# Motorsteuerung_v3.net
KiCad netlist of a schematic drawn in EAGLE
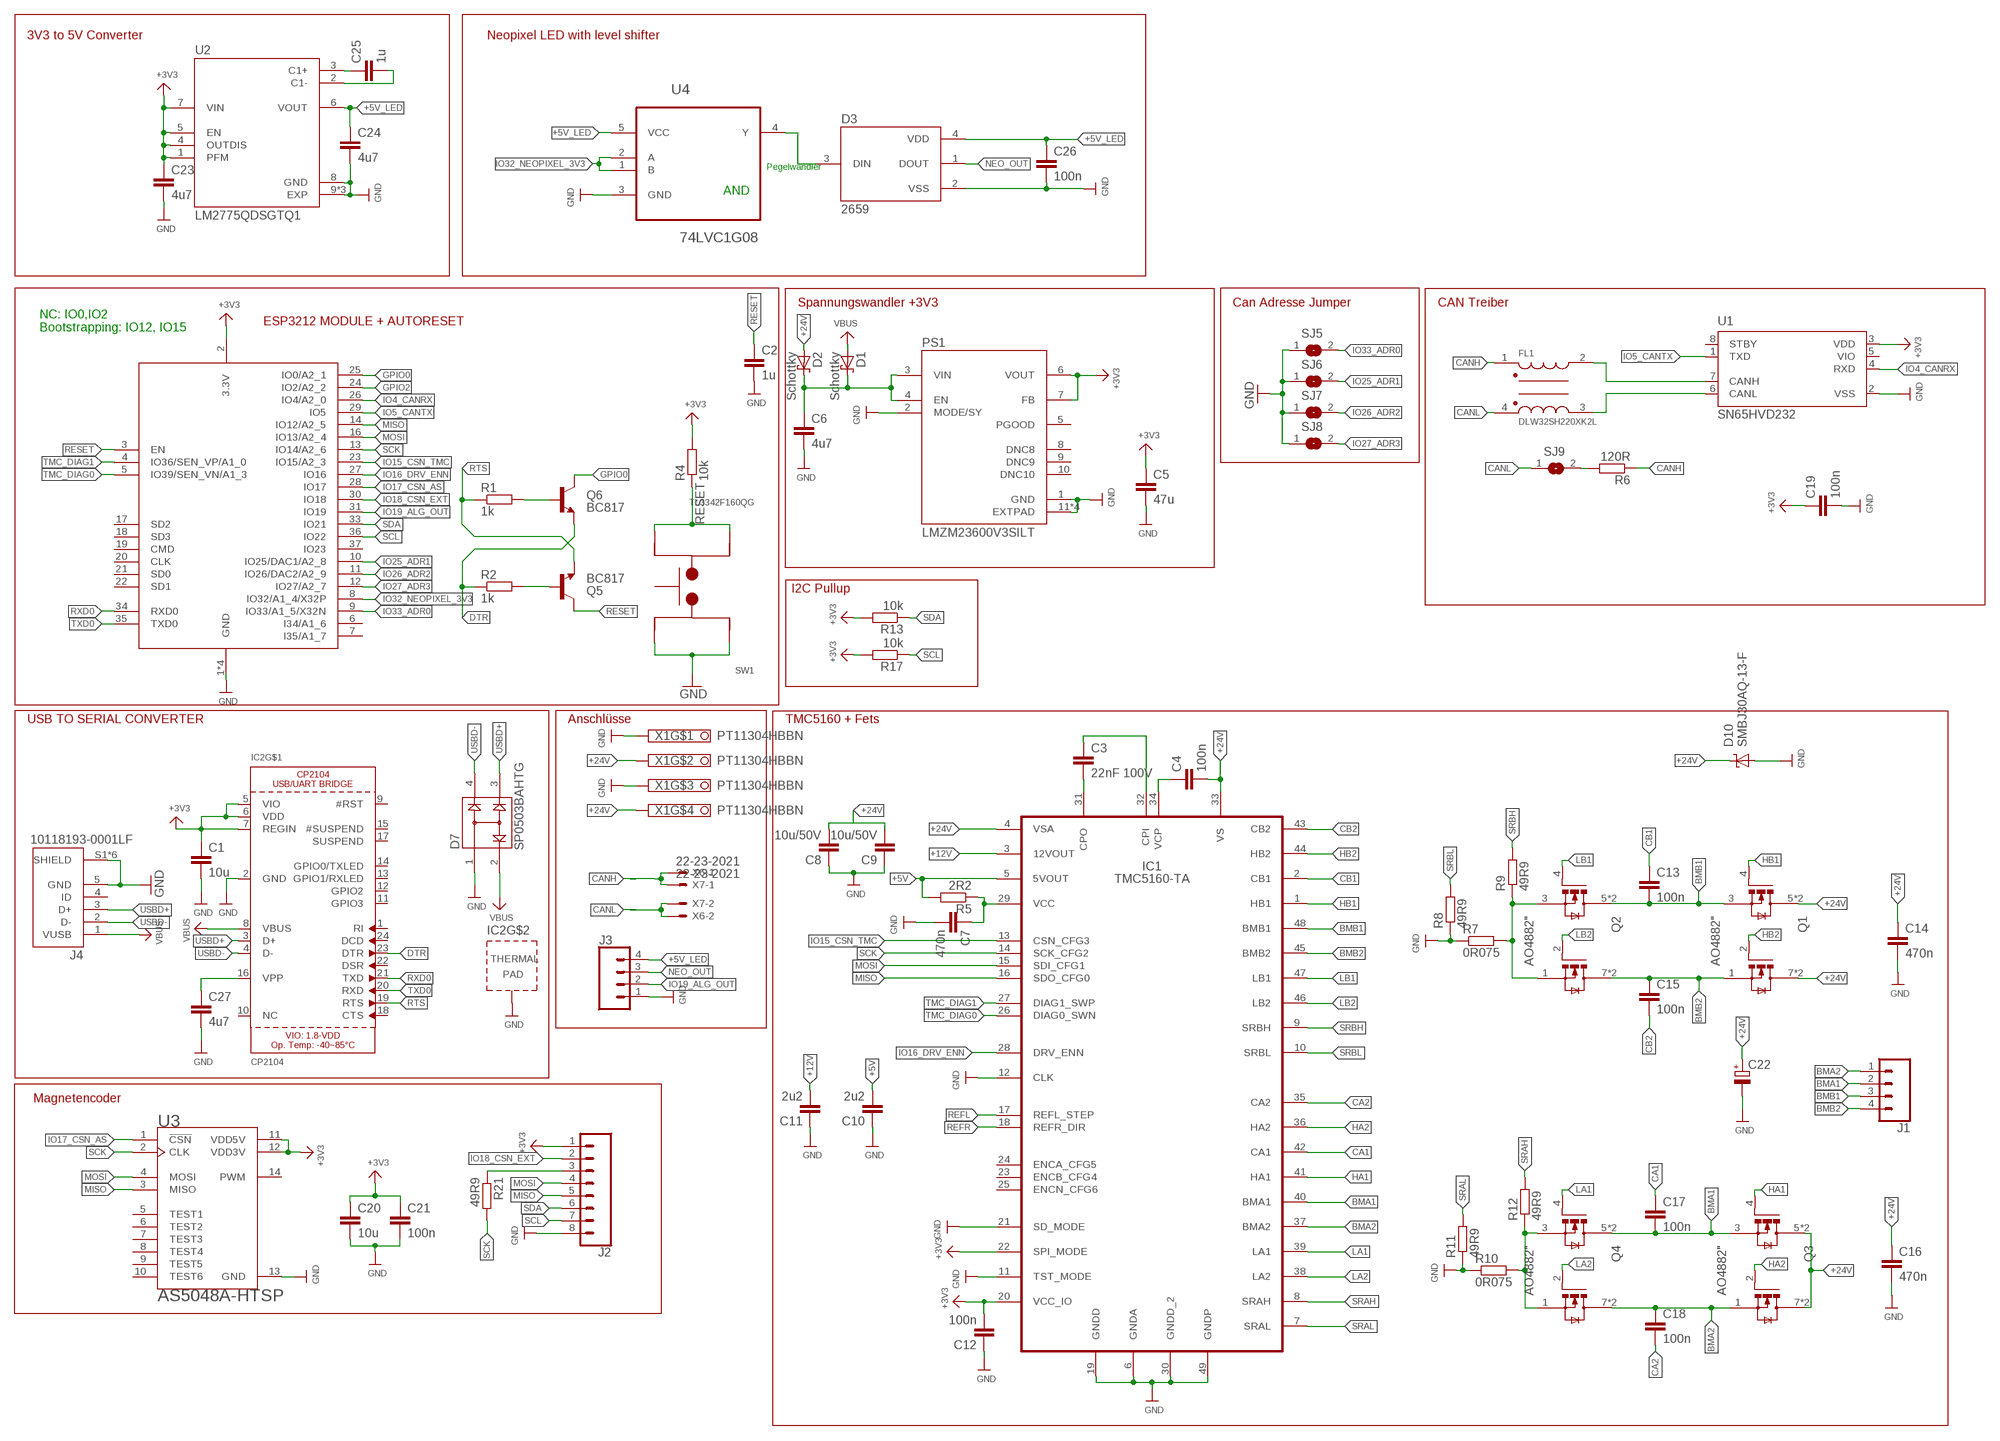
[diagram p0: schematic, sheet 1]

(export (version "E")
  (design (tool "Eeschema 10.0.6"))
  (components
    (comp (ref "C1")
      (value "10u")
      (footprint "eagle-import:C0805")
      (libsource (lib "eagle-import") (part "C-EUC0805"))
    )
    (comp (ref "C2")
      (value "1u")
      (footprint "eagle-import:C0805")
      (libsource (lib "eagle-import") (part "C-EUC0805"))
    )
    (comp (ref "C3")
      (value "22nF 100V")
      (footprint "eagle-import:C0805")
      (libsource (lib "eagle-import") (part "C-EUC0805"))
    )
    (comp (ref "C4")
      (value "100n")
      (footprint "eagle-import:C0805")
      (libsource (lib "eagle-import") (part "C-EUC0805"))
    )
    (comp (ref "C5")
      (value "47u")
      (footprint "eagle-import:C0805")
      (libsource (lib "eagle-import") (part "C-EUC0805"))
    )
    (comp (ref "C6")
      (value "4u7")
      (footprint "eagle-import:C0805")
      (libsource (lib "eagle-import") (part "C-EUC0805"))
    )
    (comp (ref "C7")
      (value "470n")
      (footprint "eagle-import:C0805")
      (libsource (lib "eagle-import") (part "C-EUC0805"))
    )
    (comp (ref "C8")
      (value "10u/50V")
      (footprint "eagle-import:C0805")
      (libsource (lib "eagle-import") (part "C-EUC0805"))
    )
    (comp (ref "C9")
      (value "10u/50V")
      (footprint "eagle-import:C0805")
      (libsource (lib "eagle-import") (part "C-EUC0805"))
    )
    (comp (ref "C10")
      (value "2u2")
      (footprint "eagle-import:C0805")
      (libsource (lib "eagle-import") (part "C-EUC0805"))
    )
    (comp (ref "C11")
      (value "2u2")
      (footprint "eagle-import:C0805")
      (libsource (lib "eagle-import") (part "C-EUC0805"))
    )
    (comp (ref "C12")
      (value "100n")
      (footprint "eagle-import:C0805")
      (libsource (lib "eagle-import") (part "C-EUC0805"))
    )
    (comp (ref "C13")
      (value "100n")
      (footprint "eagle-import:C0805")
      (libsource (lib "eagle-import") (part "C-EUC0805"))
    )
    (comp (ref "C14")
      (value "470n")
      (footprint "eagle-import:C0805")
      (libsource (lib "eagle-import") (part "C-EUC0805"))
    )
    (comp (ref "C15")
      (value "100n")
      (footprint "eagle-import:C0805")
      (libsource (lib "eagle-import") (part "C-EUC0805"))
    )
    (comp (ref "C16")
      (value "470n")
      (footprint "eagle-import:C0805")
      (libsource (lib "eagle-import") (part "C-EUC0805"))
    )
    (comp (ref "C17")
      (value "100n")
      (footprint "eagle-import:C0805")
      (libsource (lib "eagle-import") (part "C-EUC0805"))
    )
    (comp (ref "C18")
      (value "100n")
      (footprint "eagle-import:C0805")
      (libsource (lib "eagle-import") (part "C-EUC0805"))
    )
    (comp (ref "C19")
      (value "100n")
      (footprint "eagle-import:C0805")
      (libsource (lib "eagle-import") (part "C-EUC0805"))
    )
    (comp (ref "C20")
      (value "10u")
      (footprint "eagle-import:C0805")
      (libsource (lib "eagle-import") (part "C-EUC0805"))
    )
    (comp (ref "C21")
      (value "100n")
      (footprint "eagle-import:C0805")
      (libsource (lib "eagle-import") (part "C-EUC0805"))
    )
    (comp (ref "C22")
      (value "CPOL-EUE5-10.5")
      (footprint "eagle-import:E5-10,5")
      (libsource (lib "eagle-import") (part "CPOL-EUE5-10.5"))
    )
    (comp (ref "C23")
      (value "4u7")
      (footprint "eagle-import:C0805")
      (libsource (lib "eagle-import") (part "C-EUC0805"))
    )
    (comp (ref "C24")
      (value "4u7")
      (footprint "eagle-import:C0805")
      (libsource (lib "eagle-import") (part "C-EUC0805"))
    )
    (comp (ref "C25")
      (value "1u")
      (footprint "eagle-import:C0805")
      (libsource (lib "eagle-import") (part "C-EUC0805"))
    )
    (comp (ref "C26")
      (value "100n")
      (footprint "eagle-import:C0805")
      (libsource (lib "eagle-import") (part "C-EUC0805"))
    )
    (comp (ref "C27")
      (value "4u7")
      (footprint "eagle-import:C0805")
      (libsource (lib "eagle-import") (part "C-EUC0805"))
    )
    (comp (ref "D1")
      (value "Schottky")
      (footprint "eagle-import:SMB")
      (libsource (lib "eagle-import") (part "SCHOTTKY-DIODESMD"))
    )
    (comp (ref "D2")
      (value "Schottky")
      (footprint "eagle-import:SMB")
      (libsource (lib "eagle-import") (part "SCHOTTKY-DIODESMD"))
    )
    (comp (ref "D3")
      (value "2659")
      (footprint "eagle-import:2659")
      (fields (field (name "MF") "Adafruit Industries"))
      (libsource (lib "eagle-import") (part "2659"))
    )
    (comp (ref "D7")
      (value "SP0503BAHTG")
      (footprint "eagle-import:SOT143")
      (fields (field (name "MF") "Littelfuse Inc."))
      (libsource (lib "eagle-import") (part "SP0503BAHTG"))
    )
    (comp (ref "D10")
      (value "SMBJ30AQ-13-F")
      (footprint "eagle-import:SMBJ")
      (libsource (lib "eagle-import") (part "SUPPRESSOR-SMBJ"))
    )
    (comp (ref "FL1")
      (value "DLW32SH220XK2L")
      (footprint "eagle-import:FIL_DLW32SH110XK2L")
      (fields (field (name "MF") "Murata") (field (name "MP") "DLW32SH110XK2L"))
      (libsource (lib "eagle-import") (part "DLW32SH110XK2L"))
    )
    (comp (ref "IC1")
      (value "TMC5160-TA")
      (footprint "eagle-import:TQFP48-EP")
      (fields (field (name "MF") "Trinamic Motion"))
      (libsource (lib "eagle-import") (part "TMC5160-TA"))
    )
    (comp (ref "IC2")
      (value "CP2104")
      (footprint "eagle-import:QFN24_4MM_SMSC")
      (libsource (lib "eagle-import") (part "CP2104"))
    )
    (comp (ref "J1")
      (value "CONN_04")
      (footprint "eagle-import:1X04")
      (libsource (lib "eagle-import") (part "CONN_04"))
    )
    (comp (ref "J2")
      (value "CONN_08BM08B-SRSS-TB")
      (footprint "eagle-import:BM08B-SRSS-TB")
      (libsource (lib "eagle-import") (part "CONN_08BM08B-SRSS-TB"))
    )
    (comp (ref "J3")
      (value "CONN_041.27MM")
      (footprint "eagle-import:1X04_1.27MM")
      (libsource (lib "eagle-import") (part "CONN_041.27MM"))
    )
    (comp (ref "J4")
      (value "10118193-0001LF")
      (footprint "eagle-import:FCI_10118193-0001LF")
      (fields (field (name "MF") "Amphenol ICC (FCI)"))
      (libsource (lib "eagle-import") (part "10118193-0001LF"))
    )
    (comp (ref "PS1")
      (value "LMZM23600V3SILT")
      (footprint "eagle-import:CONV_LMZM23600V3SILT")
      (fields (field (name "MF") "Texas Instruments"))
      (libsource (lib "eagle-import") (part "LMZM23600V3SILT"))
    )
    (comp (ref "Q1")
      (value "AO4882\"")
      (footprint "eagle-import:SOIC8")
      (libsource (lib "eagle-import") (part "AO4882{dblquote}"))
    )
    (comp (ref "Q2")
      (value "AO4882\"")
      (footprint "eagle-import:SOIC8")
      (libsource (lib "eagle-import") (part "AO4882{dblquote}"))
    )
    (comp (ref "Q3")
      (value "AO4882\"")
      (footprint "eagle-import:SOIC8")
      (libsource (lib "eagle-import") (part "AO4882{dblquote}"))
    )
    (comp (ref "Q4")
      (value "AO4882\"")
      (footprint "eagle-import:SOIC8")
      (libsource (lib "eagle-import") (part "AO4882{dblquote}"))
    )
    (comp (ref "Q5")
      (value "BC817")
      (footprint "eagle-import:SOT23-3")
      (libsource (lib "eagle-import") (part "TRANSISTOR_NPNSOT23-3"))
    )
    (comp (ref "Q6")
      (value "BC817")
      (footprint "eagle-import:SOT23-3")
      (libsource (lib "eagle-import") (part "TRANSISTOR_NPNSOT23-3"))
    )
    (comp (ref "R1")
      (value "1k")
      (footprint "eagle-import:R0805")
      (libsource (lib "eagle-import") (part "R-EU_R0805"))
    )
    (comp (ref "R2")
      (value "1k")
      (footprint "eagle-import:R0805")
      (libsource (lib "eagle-import") (part "R-EU_R0805"))
    )
    (comp (ref "R4")
      (value "10k")
      (footprint "eagle-import:R0805")
      (libsource (lib "eagle-import") (part "R-EU_R0805"))
    )
    (comp (ref "R5")
      (value "2R2")
      (footprint "eagle-import:R0805")
      (libsource (lib "eagle-import") (part "R-EU_R0805"))
    )
    (comp (ref "R6")
      (value "120R")
      (footprint "eagle-import:R0805")
      (libsource (lib "eagle-import") (part "R-EU_R0805"))
    )
    (comp (ref "R7")
      (value "0R075")
      (footprint "eagle-import:R1206")
      (libsource (lib "eagle-import") (part "R-EU_R1206"))
    )
    (comp (ref "R8")
      (value "49R9")
      (footprint "eagle-import:R0805")
      (libsource (lib "eagle-import") (part "R-EU_R0805"))
    )
    (comp (ref "R9")
      (value "49R9")
      (footprint "eagle-import:R0805")
      (libsource (lib "eagle-import") (part "R-EU_R0805"))
    )
    (comp (ref "R10")
      (value "0R075")
      (footprint "eagle-import:R1206")
      (libsource (lib "eagle-import") (part "R-EU_R1206"))
    )
    (comp (ref "R11")
      (value "49R9")
      (footprint "eagle-import:R0805")
      (libsource (lib "eagle-import") (part "R-EU_R0805"))
    )
    (comp (ref "R12")
      (value "49R9")
      (footprint "eagle-import:R0805")
      (libsource (lib "eagle-import") (part "R-EU_R0805"))
    )
    (comp (ref "R13")
      (value "10k")
      (footprint "eagle-import:R0805")
      (libsource (lib "eagle-import") (part "R-EU_R0805"))
    )
    (comp (ref "R17")
      (value "10k")
      (footprint "eagle-import:R0805")
      (libsource (lib "eagle-import") (part "R-EU_R0805"))
    )
    (comp (ref "R21")
      (value "49R9")
      (footprint "eagle-import:R0805")
      (libsource (lib "eagle-import") (part "R-EU_R0805"))
    )
    (comp (ref "SJ5") (value "SJ") (footprint "eagle-import:SJ") (libsource (lib "eagle-import") (part "SJ")))
    (comp (ref "SJ6") (value "SJ") (footprint "eagle-import:SJ") (libsource (lib "eagle-import") (part "SJ")))
    (comp (ref "SJ7") (value "SJ") (footprint "eagle-import:SJ") (libsource (lib "eagle-import") (part "SJ")))
    (comp (ref "SJ8") (value "SJ") (footprint "eagle-import:SJ") (libsource (lib "eagle-import") (part "SJ")))
    (comp (ref "SJ9") (value "SJ") (footprint "eagle-import:SJ") (libsource (lib "eagle-import") (part "SJ")))
    (comp (ref "SW1")
      (value "TL3342F160QG")
      (footprint "eagle-import:SW_TL3342F160QG")
      (fields (field (name "MF") "E-Switch"))
      (libsource (lib "eagle-import") (part "TL3342F160QG"))
    )
    (comp (ref "U1")
      (value "SN65HVD232")
      (footprint "eagle-import:SOIC127P600X175-8N")
      (fields (field (name "MF") "Microchip") (field (name "MP") "MCP2562-E/SN"))
      (libsource (lib "eagle-import") (part "MCP2562-E/SN"))
    )
    (comp (ref "U2")
      (value "LM2775QDSGTQ1")
      (footprint "eagle-import:SON50P200X200X80-9N")
      (fields (field (name "MF") "Texas Instruments"))
      (libsource (lib "eagle-import") (part "LM2775QDSGTQ1"))
    )
    (comp (ref "U3")
      (value "AS5048A-HTSP")
      (footprint "eagle-import:SOP65P640X120-14N")
      (fields (field (name "MF") "ams"))
      (libsource (lib "eagle-import") (part "AS5048A-HTSP"))
    )
    (comp (ref "U4")
      (value "74LVC1G08")
      (footprint "eagle-import:SOT65P210X110-5N")
      (fields (field (name "MF") "Nexperia") (field (name "MP") "74LVC1G00GW"))
      (libsource (lib "eagle-import") (part "74LVC1G00GW"))
    )
    (comp (ref "X1")
      (value "PT11304HBBN")
      (footprint "eagle-import:TYP184_FT")
      (libsource (lib "eagle-import") (part "TYP184"))
    )
    (comp (ref "X2")
      (value "ESP32_WROOM32_SKINNY")
      (footprint "eagle-import:WROOM32_SKINNY")
      (libsource (lib "eagle-import") (part "ESP32_WROOM32_SKINNY"))
    )
    (comp (ref "X6")
      (value "22-23-2021")
      (footprint "eagle-import:22-23-2021")
      (fields (field (name "MF") "MOLEX"))
      (libsource (lib "eagle-import") (part "22-23-2021"))
    )
    (comp (ref "X7")
      (value "22-23-2021")
      (footprint "eagle-import:22-23-2021")
      (fields (field (name "MF") "MOLEX"))
      (libsource (lib "eagle-import") (part "22-23-2021"))
    )
  )
  (nets
    (net (code "1") (name "+3V3") (class "Default")
      (node (ref "C1") (pin "1") (pinfunction "1_1") (pintype "passive"))
      (node (ref "C12") (pin "2") (pinfunction "2_2") (pintype "passive"))
      (node (ref "C19") (pin "1") (pinfunction "1_1") (pintype "passive"))
      (node (ref "C20") (pin "1") (pinfunction "1_1") (pintype "passive"))
      (node (ref "C21") (pin "1") (pinfunction "1_1") (pintype "passive"))
      (node (ref "C23") (pin "1") (pinfunction "1_1") (pintype "passive"))
      (node (ref "C5") (pin "1") (pinfunction "1_1") (pintype "passive"))
      (node (ref "IC1") (pin "20") (pinfunction "VCC_IO_20") (pintype "power_in"))
      (node (ref "IC1") (pin "22") (pinfunction "SPI_MODE_22") (pintype "input"))
      (node (ref "IC2") (pin "5") (pinfunction "VIO_5") (pintype "power_in"))
      (node (ref "IC2") (pin "6") (pinfunction "VDD_6") (pintype "power_in"))
      (node (ref "IC2") (pin "7") (pinfunction "REGIN_7") (pintype "power_in"))
      (node (ref "J2") (pin "1") (pinfunction "1_1") (pintype "passive"))
      (node (ref "PS1") (pin "6") (pinfunction "VOUT_6") (pintype "output"))
      (node (ref "PS1") (pin "7") (pinfunction "FB_7") (pintype "input"))
      (node (ref "R13") (pin "2") (pinfunction "2_2") (pintype "passive"))
      (node (ref "R17") (pin "2") (pinfunction "2_2") (pintype "passive"))
      (node (ref "R4") (pin "2") (pinfunction "2_2") (pintype "passive"))
      (node (ref "U1") (pin "3") (pinfunction "VDD_3") (pintype "power_in"))
      (node (ref "U2") (pin "1") (pinfunction "PFM_1") (pintype "input"))
      (node (ref "U2") (pin "4") (pinfunction "OUTDIS_4") (pintype "input"))
      (node (ref "U2") (pin "5") (pinfunction "EN_5") (pintype "input"))
      (node (ref "U2") (pin "7") (pinfunction "VIN_7") (pintype "input"))
      (node (ref "U3") (pin "11") (pinfunction "VDD5V_11") (pintype "power_in"))
      (node (ref "U3") (pin "12") (pinfunction "VDD3V_12") (pintype "power_in"))
      (node (ref "X2") (pin "2") (pinfunction "3.3V_2") (pintype "passive"))
    )
    (net (code "2") (name "+5V") (class "Default")
      (node (ref "C10") (pin "2") (pinfunction "2_2") (pintype "passive"))
      (node (ref "IC1") (pin "5") (pinfunction "5VOUT_5") (pintype "bidirectional"))
      (node (ref "R5") (pin "2") (pinfunction "2_2") (pintype "passive"))
    )
    (net (code "3") (name "+5V_LED") (class "Default")
      (node (ref "C24") (pin "1") (pinfunction "1_1") (pintype "passive"))
      (node (ref "C26") (pin "1") (pinfunction "1_1") (pintype "passive"))
      (node (ref "D3") (pin "4") (pinfunction "VDD_4") (pintype "power_in"))
      (node (ref "J3") (pin "4") (pinfunction "4_4") (pintype "passive"))
      (node (ref "U2") (pin "6") (pinfunction "VOUT_6") (pintype "output"))
      (node (ref "U4") (pin "5") (pinfunction "VCC_5") (pintype "power_in"))
    )
    (net (code "4") (name "+12V") (class "Default")
      (node (ref "C11") (pin "2") (pinfunction "2_2") (pintype "passive"))
      (node (ref "IC1") (pin "3") (pinfunction "12VOUT_3") (pintype "bidirectional"))
    )
    (net (code "5") (name "+24V") (class "Default")
      (node (ref "C14") (pin "1") (pinfunction "1_1") (pintype "passive"))
      (node (ref "C16") (pin "1") (pinfunction "1_1") (pintype "passive"))
      (node (ref "C22") (pin "+") (pinfunction "+_+") (pintype "passive"))
      (node (ref "C4") (pin "2") (pinfunction "2_2") (pintype "passive"))
      (node (ref "C8") (pin "2") (pinfunction "2_2") (pintype "passive"))
      (node (ref "C9") (pin "2") (pinfunction "2_2") (pintype "passive"))
      (node (ref "D10") (pin "C") (pinfunction "C_C") (pintype "passive"))
      (node (ref "D2") (pin "A") (pinfunction "A_A") (pintype "passive"))
      (node (ref "IC1") (pin "33") (pinfunction "VS_33") (pintype "power_in"))
      (node (ref "IC1") (pin "4") (pinfunction "VSA_4") (pintype "power_in"))
      (node (ref "Q1") (pin "5") (pinfunction "D1_5") (pintype "passive"))
      (node (ref "Q1") (pin "6") (pinfunction "D1_6") (pintype "passive"))
      (node (ref "Q1") (pin "7") (pinfunction "D2_7") (pintype "passive"))
      (node (ref "Q1") (pin "8") (pinfunction "D2_8") (pintype "passive"))
      (node (ref "Q3") (pin "5") (pinfunction "D1_5") (pintype "passive"))
      (node (ref "Q3") (pin "6") (pinfunction "D1_6") (pintype "passive"))
      (node (ref "Q3") (pin "7") (pinfunction "D2_7") (pintype "passive"))
      (node (ref "Q3") (pin "8") (pinfunction "D2_8") (pintype "passive"))
      (node (ref "X1") (pin "2") (pinfunction "K_2") (pintype "passive"))
      (node (ref "X1") (pin "4") (pinfunction "K_4") (pintype "passive"))
    )
    (net (code "6") (name "/VIO") (class "Default")
      (node (ref "U1") (pin "5") (pinfunction "VIO_5") (pintype "power_in"))
    )
    (net (code "7") (name "BMA1") (class "Default")
      (node (ref "C17") (pin "2") (pinfunction "2_2") (pintype "passive"))
      (node (ref "IC1") (pin "40") (pinfunction "BMA1_40") (pintype "input"))
      (node (ref "J1") (pin "2") (pinfunction "2_2") (pintype "passive"))
      (node (ref "Q3") (pin "3") (pinfunction "S1_3") (pintype "passive"))
      (node (ref "Q4") (pin "5") (pinfunction "D1_5") (pintype "passive"))
      (node (ref "Q4") (pin "6") (pinfunction "D1_6") (pintype "passive"))
    )
    (net (code "8") (name "BMA2") (class "Default")
      (node (ref "C18") (pin "1") (pinfunction "1_1") (pintype "passive"))
      (node (ref "IC1") (pin "37") (pinfunction "BMA2_37") (pintype "input"))
      (node (ref "J1") (pin "1") (pinfunction "1_1") (pintype "passive"))
      (node (ref "Q3") (pin "1") (pinfunction "S2_1") (pintype "passive"))
      (node (ref "Q4") (pin "7") (pinfunction "D2_7") (pintype "passive"))
      (node (ref "Q4") (pin "8") (pinfunction "D2_8") (pintype "passive"))
    )
    (net (code "9") (name "BMB1") (class "Default")
      (node (ref "C13") (pin "2") (pinfunction "2_2") (pintype "passive"))
      (node (ref "IC1") (pin "48") (pinfunction "BMB1_48") (pintype "input"))
      (node (ref "J1") (pin "3") (pinfunction "3_3") (pintype "passive"))
      (node (ref "Q1") (pin "3") (pinfunction "S1_3") (pintype "passive"))
      (node (ref "Q2") (pin "5") (pinfunction "D1_5") (pintype "passive"))
      (node (ref "Q2") (pin "6") (pinfunction "D1_6") (pintype "passive"))
    )
    (net (code "10") (name "BMB2") (class "Default")
      (node (ref "C15") (pin "1") (pinfunction "1_1") (pintype "passive"))
      (node (ref "IC1") (pin "45") (pinfunction "BMB2_45") (pintype "input"))
      (node (ref "J1") (pin "4") (pinfunction "4_4") (pintype "passive"))
      (node (ref "Q1") (pin "1") (pinfunction "S2_1") (pintype "passive"))
      (node (ref "Q2") (pin "7") (pinfunction "D2_7") (pintype "passive"))
      (node (ref "Q2") (pin "8") (pinfunction "D2_8") (pintype "passive"))
    )
    (net (code "11") (name "CA1") (class "Default")
      (node (ref "C17") (pin "1") (pinfunction "1_1") (pintype "passive"))
      (node (ref "IC1") (pin "42") (pinfunction "CA1_42") (pintype "input"))
    )
    (net (code "12") (name "CA2") (class "Default")
      (node (ref "C18") (pin "2") (pinfunction "2_2") (pintype "passive"))
      (node (ref "IC1") (pin "35") (pinfunction "CA2_35") (pintype "input"))
    )
    (net (code "13") (name "CANH") (class "Default")
      (node (ref "FL1") (pin "1") (pinfunction "1_1") (pintype "passive"))
      (node (ref "R6") (pin "1") (pinfunction "1_1") (pintype "passive"))
      (node (ref "X6") (pin "1") (pinfunction "S_1") (pintype "passive"))
      (node (ref "X7") (pin "1") (pinfunction "S_1") (pintype "passive"))
    )
    (net (code "14") (name "CANL") (class "Default")
      (node (ref "FL1") (pin "4") (pinfunction "4_4") (pintype "passive"))
      (node (ref "SJ9") (pin "1") (pinfunction "1_1") (pintype "passive"))
      (node (ref "X6") (pin "2") (pinfunction "S_2") (pintype "passive"))
      (node (ref "X7") (pin "2") (pinfunction "S_2") (pintype "passive"))
    )
    (net (code "15") (name "CB1") (class "Default")
      (node (ref "C13") (pin "1") (pinfunction "1_1") (pintype "passive"))
      (node (ref "IC1") (pin "2") (pinfunction "CB1_2") (pintype "input"))
    )
    (net (code "16") (name "CB2") (class "Default")
      (node (ref "C15") (pin "2") (pinfunction "2_2") (pintype "passive"))
      (node (ref "IC1") (pin "43") (pinfunction "CB2_43") (pintype "input"))
    )
    (net (code "17") (name "DTR") (class "Default")
      (node (ref "IC2") (pin "23") (pinfunction "DTR_23") (pintype "output"))
      (node (ref "Q6") (pin "2") (pinfunction "E_2") (pintype "passive"))
      (node (ref "R2") (pin "1") (pinfunction "1_1") (pintype "passive"))
    )
    (net (code "18") (name "GND") (class "Default")
      (node (ref "C1") (pin "2") (pinfunction "2_2") (pintype "passive"))
      (node (ref "C10") (pin "1") (pinfunction "1_1") (pintype "passive"))
      (node (ref "C11") (pin "1") (pinfunction "1_1") (pintype "passive"))
      (node (ref "C12") (pin "1") (pinfunction "1_1") (pintype "passive"))
      (node (ref "C14") (pin "2") (pinfunction "2_2") (pintype "passive"))
      (node (ref "C16") (pin "2") (pinfunction "2_2") (pintype "passive"))
      (node (ref "C19") (pin "2") (pinfunction "2_2") (pintype "passive"))
      (node (ref "C2") (pin "2") (pinfunction "2_2") (pintype "passive"))
      (node (ref "C20") (pin "2") (pinfunction "2_2") (pintype "passive"))
      (node (ref "C21") (pin "2") (pinfunction "2_2") (pintype "passive"))
      (node (ref "C22") (pin "-") (pinfunction "-_-") (pintype "passive"))
      (node (ref "C23") (pin "2") (pinfunction "2_2") (pintype "passive"))
      (node (ref "C24") (pin "2") (pinfunction "2_2") (pintype "passive"))
      (node (ref "C26") (pin "2") (pinfunction "2_2") (pintype "passive"))
      (node (ref "C27") (pin "2") (pinfunction "2_2") (pintype "passive"))
      (node (ref "C5") (pin "2") (pinfunction "2_2") (pintype "passive"))
      (node (ref "C6") (pin "2") (pinfunction "2_2") (pintype "passive"))
      (node (ref "C7") (pin "2") (pinfunction "2_2") (pintype "passive"))
      (node (ref "C8") (pin "1") (pinfunction "1_1") (pintype "passive"))
      (node (ref "C9") (pin "1") (pinfunction "1_1") (pintype "passive"))
      (node (ref "D10") (pin "A") (pinfunction "A_A") (pintype "passive"))
      (node (ref "D3") (pin "2") (pinfunction "VSS_2") (pintype "power_in"))
      (node (ref "D7") (pin "1") (pinfunction "1_1") (pintype "passive"))
      (node (ref "IC1") (pin "11") (pinfunction "TST_MODE_11") (pintype "input"))
      (node (ref "IC1") (pin "12") (pinfunction "CLK_12") (pintype "input"))
      (node (ref "IC1") (pin "19") (pinfunction "GNDD_19") (pintype "power_in"))
      (node (ref "IC1") (pin "21") (pinfunction "SD_MODE_21") (pintype "input"))
      (node (ref "IC1") (pin "30") (pinfunction "GNDD_2_30") (pintype "power_in"))
      (node (ref "IC1") (pin "49") (pinfunction "GNDP_49") (pintype "power_in"))
      (node (ref "IC1") (pin "6") (pinfunction "GNDA_6") (pintype "power_in"))
      (node (ref "IC2") (pin "2") (pinfunction "GND_2") (pintype "power_in"))
      (node (ref "IC2") (pin "THERM") (pinfunction "TP_THERM") (pintype "power_in"))
      (node (ref "J2") (pin "8") (pinfunction "8_8") (pintype "passive"))
      (node (ref "J3") (pin "1") (pinfunction "1_1") (pintype "passive"))
      (node (ref "J4") (pin "5") (pinfunction "GND_5") (pintype "passive"))
      (node (ref "J4") (pin "S1") (pinfunction "SHIELD_S1") (pintype "passive"))
      (node (ref "J4") (pin "S2") (pinfunction "SHIELD_S2") (pintype "passive"))
      (node (ref "J4") (pin "S3") (pinfunction "SHIELD_S3") (pintype "passive"))
      (node (ref "J4") (pin "S4") (pinfunction "SHIELD_S4") (pintype "passive"))
      (node (ref "J4") (pin "S5") (pinfunction "SHIELD_S5") (pintype "passive"))
      (node (ref "J4") (pin "S6") (pinfunction "SHIELD_S6") (pintype "passive"))
      (node (ref "PS1") (pin "1") (pinfunction "GND_1") (pintype "power_in"))
      (node (ref "PS1") (pin "11") (pinfunction "EXTPAD_11") (pintype "power_in"))
      (node (ref "PS1") (pin "11_1") (pinfunction "EXTPAD_11_1") (pintype "power_in"))
      (node (ref "PS1") (pin "11_2") (pinfunction "EXTPAD_11_2") (pintype "power_in"))
      (node (ref "PS1") (pin "11_3") (pinfunction "EXTPAD_11_3") (pintype "power_in"))
      (node (ref "PS1") (pin "2") (pinfunction "MODE/SY_2") (pintype "input"))
      (node (ref "R10") (pin "1") (pinfunction "1_1") (pintype "passive"))
      (node (ref "R11") (pin "1") (pinfunction "1_1") (pintype "passive"))
      (node (ref "R7") (pin "1") (pinfunction "1_1") (pintype "passive"))
      (node (ref "R8") (pin "1") (pinfunction "1_1") (pintype "passive"))
      (node (ref "SJ5") (pin "1") (pinfunction "1_1") (pintype "passive"))
      (node (ref "SJ6") (pin "1") (pinfunction "1_1") (pintype "passive"))
      (node (ref "SJ7") (pin "1") (pinfunction "1_1") (pintype "passive"))
      (node (ref "SJ8") (pin "1") (pinfunction "1_1") (pintype "passive"))
      (node (ref "SW1") (pin "3") (pinfunction "3_3") (pintype "passive"))
      (node (ref "SW1") (pin "4") (pinfunction "4_4") (pintype "passive"))
      (node (ref "U1") (pin "2") (pinfunction "VSS_2") (pintype "power_in"))
      (node (ref "U2") (pin "8") (pinfunction "GND_8") (pintype "power_in"))
      (node (ref "U2") (pin "9") (pinfunction "EXP_9") (pintype "power_in"))
      (node (ref "U2") (pin "9_1") (pinfunction "EXP_9_1") (pintype "power_in"))
      (node (ref "U2") (pin "9_2") (pinfunction "EXP_9_2") (pintype "power_in"))
      (node (ref "U3") (pin "13") (pinfunction "GND_13") (pintype "passive"))
      (node (ref "U4") (pin "3") (pinfunction "GND_3") (pintype "passive"))
      (node (ref "X1") (pin "1") (pinfunction "K_1") (pintype "passive"))
      (node (ref "X1") (pin "3") (pinfunction "K_3") (pintype "passive"))
      (node (ref "X2") (pin "1") (pinfunction "GND_1") (pintype "passive"))
      (node (ref "X2") (pin "15") (pinfunction "GND_15") (pintype "passive"))
      (node (ref "X2") (pin "38") (pinfunction "GND_38") (pintype "passive"))
      (node (ref "X2") (pin "P$1") (pinfunction "GND_P$1") (pintype "passive"))
    )
    (net (code "19") (name "GPIO0") (class "Default")
      (node (ref "Q6") (pin "3") (pinfunction "C_3") (pintype "passive"))
      (node (ref "X2") (pin "25") (pinfunction "IO0/A2_1_25") (pintype "bidirectional"))
    )
    (net (code "20") (name "GPIO2") (class "Default")
      (node (ref "X2") (pin "24") (pinfunction "IO2/A2_2_24") (pintype "bidirectional"))
    )
    (net (code "21") (name "HA1") (class "Default")
      (node (ref "IC1") (pin "41") (pinfunction "HA1_41") (pintype "output"))
      (node (ref "Q3") (pin "4") (pinfunction "G1_4") (pintype "passive"))
    )
    (net (code "22") (name "HA2") (class "Default")
      (node (ref "IC1") (pin "36") (pinfunction "HA2_36") (pintype "output"))
      (node (ref "Q3") (pin "2") (pinfunction "G2_2") (pintype "passive"))
    )
    (net (code "23") (name "HB1") (class "Default")
      (node (ref "IC1") (pin "1") (pinfunction "HB1_1") (pintype "output"))
      (node (ref "Q1") (pin "4") (pinfunction "G1_4") (pintype "passive"))
    )
    (net (code "24") (name "HB2") (class "Default")
      (node (ref "IC1") (pin "44") (pinfunction "HB2_44") (pintype "output"))
      (node (ref "Q1") (pin "2") (pinfunction "G2_2") (pintype "passive"))
    )
    (net (code "25") (name "IO4_CANRX") (class "Default")
      (node (ref "U1") (pin "4") (pinfunction "RXD_4") (pintype "output"))
      (node (ref "X2") (pin "26") (pinfunction "IO4/A2_0_26") (pintype "bidirectional"))
    )
    (net (code "26") (name "IO5_CANTX") (class "Default")
      (node (ref "U1") (pin "1") (pinfunction "TXD_1") (pintype "input"))
      (node (ref "X2") (pin "29") (pinfunction "IO5_29") (pintype "bidirectional"))
    )
    (net (code "27") (name "IO15_CSN_TMC") (class "Default")
      (node (ref "IC1") (pin "13") (pinfunction "CSN_CFG3_13") (pintype "input"))
      (node (ref "X2") (pin "23") (pinfunction "IO15/A2_3_23") (pintype "bidirectional"))
    )
    (net (code "28") (name "IO16_DRV_ENN") (class "Default")
      (node (ref "IC1") (pin "28") (pinfunction "DRV_ENN_28") (pintype "input"))
      (node (ref "X2") (pin "27") (pinfunction "IO16_27") (pintype "bidirectional"))
    )
    (net (code "29") (name "IO17_CSN_AS") (class "Default")
      (node (ref "U3") (pin "1") (pinfunction "~{CSN}_1") (pintype "input"))
      (node (ref "X2") (pin "28") (pinfunction "IO17_28") (pintype "bidirectional"))
    )
    (net (code "30") (name "IO18_CSN_EXT") (class "Default")
      (node (ref "J2") (pin "2") (pinfunction "2_2") (pintype "passive"))
      (node (ref "X2") (pin "30") (pinfunction "IO18_30") (pintype "bidirectional"))
    )
    (net (code "31") (name "IO19_ALG_OUT") (class "Default")
      (node (ref "J3") (pin "2") (pinfunction "2_2") (pintype "passive"))
      (node (ref "X2") (pin "31") (pinfunction "IO19_31") (pintype "bidirectional"))
    )
    (net (code "32") (name "IO25_ADR1") (class "Default")
      (node (ref "SJ6") (pin "2") (pinfunction "2_2") (pintype "passive"))
      (node (ref "X2") (pin "10") (pinfunction "IO25/DAC1/A2_8_10") (pintype "bidirectional"))
    )
    (net (code "33") (name "IO26_ADR2") (class "Default")
      (node (ref "SJ7") (pin "2") (pinfunction "2_2") (pintype "passive"))
      (node (ref "X2") (pin "11") (pinfunction "IO26/DAC2/A2_9_11") (pintype "bidirectional"))
    )
    (net (code "34") (name "IO27_ADR3") (class "Default")
      (node (ref "SJ8") (pin "2") (pinfunction "2_2") (pintype "passive"))
      (node (ref "X2") (pin "12") (pinfunction "IO27/A2_7_12") (pintype "bidirectional"))
    )
    (net (code "35") (name "IO32_NEOPIXEL_3V3") (class "Default")
      (node (ref "U4") (pin "1") (pinfunction "B_1") (pintype "input"))
      (node (ref "U4") (pin "2") (pinfunction "A_2") (pintype "input"))
      (node (ref "X2") (pin "8") (pinfunction "IO32/A1_4/X32P_8") (pintype "bidirectional"))
    )
    (net (code "36") (name "IO33_ADR0") (class "Default")
      (node (ref "SJ5") (pin "2") (pinfunction "2_2") (pintype "passive"))
      (node (ref "X2") (pin "9") (pinfunction "IO33/A1_5/X32N_9") (pintype "bidirectional"))
    )
    (net (code "37") (name "LA1") (class "Default")
      (node (ref "IC1") (pin "39") (pinfunction "LA1_39") (pintype "output"))
      (node (ref "Q4") (pin "4") (pinfunction "G1_4") (pintype "passive"))
    )
    (net (code "38") (name "LA2") (class "Default")
      (node (ref "IC1") (pin "38") (pinfunction "LA2_38") (pintype "output"))
      (node (ref "Q4") (pin "2") (pinfunction "G2_2") (pintype "passive"))
    )
    (net (code "39") (name "LB1") (class "Default")
      (node (ref "IC1") (pin "47") (pinfunction "LB1_47") (pintype "output"))
      (node (ref "Q2") (pin "4") (pinfunction "G1_4") (pintype "passive"))
    )
    (net (code "40") (name "LB2") (class "Default")
      (node (ref "IC1") (pin "46") (pinfunction "LB2_46") (pintype "output"))
      (node (ref "Q2") (pin "2") (pinfunction "G2_2") (pintype "passive"))
    )
    (net (code "41") (name "MISO") (class "Default")
      (node (ref "IC1") (pin "16") (pinfunction "SDO_CFG0_16") (pintype "output"))
      (node (ref "J2") (pin "5") (pinfunction "5_5") (pintype "passive"))
      (node (ref "U3") (pin "3") (pinfunction "MISO_3") (pintype "bidirectional"))
      (node (ref "X2") (pin "14") (pinfunction "IO12/A2_5_14") (pintype "bidirectional"))
    )
    (net (code "42") (name "MOSI") (class "Default")
      (node (ref "IC1") (pin "15") (pinfunction "SDI_CFG1_15") (pintype "input"))
      (node (ref "J2") (pin "4") (pinfunction "4_4") (pintype "passive"))
      (node (ref "U3") (pin "4") (pinfunction "MOSI_4") (pintype "input"))
      (node (ref "X2") (pin "16") (pinfunction "IO13/A2_4_16") (pintype "bidirectional"))
    )
    (net (code "43") (name "NEO_OUT") (class "Default")
      (node (ref "D3") (pin "1") (pinfunction "DOUT_1") (pintype "output"))
      (node (ref "J3") (pin "3") (pinfunction "3_3") (pintype "passive"))
    )
    (net (code "44") (name "Net-(D3-DIN)") (class "Default")
      (node (ref "D3") (pin "3") (pinfunction "DIN_3") (pintype "input"))
      (node (ref "U4") (pin "4") (pinfunction "Y_4") (pintype "output"))
    )
    (net (code "45") (name "Net-(IC1-CPI)") (class "Default")
      (node (ref "C3") (pin "1") (pinfunction "1_1") (pintype "passive"))
      (node (ref "IC1") (pin "32") (pinfunction "CPI_32") (pintype "input"))
    )
    (net (code "46") (name "Net-(IC1-CPO)") (class "Default")
      (node (ref "C3") (pin "2") (pinfunction "2_2") (pintype "passive"))
      (node (ref "IC1") (pin "31") (pinfunction "CPO_31") (pintype "input"))
    )
    (net (code "47") (name "Net-(IC1-VCC)") (class "Default")
      (node (ref "C7") (pin "1") (pinfunction "1_1") (pintype "passive"))
      (node (ref "IC1") (pin "29") (pinfunction "VCC_29") (pintype "power_in"))
      (node (ref "R5") (pin "1") (pinfunction "1_1") (pintype "passive"))
    )
    (net (code "48") (name "Net-(IC1-VCP)") (class "Default")
      (node (ref "C4") (pin "1") (pinfunction "1_1") (pintype "passive"))
      (node (ref "IC1") (pin "34") (pinfunction "VCP_34") (pintype "input"))
    )
    (net (code "49") (name "Net-(IC2A-VPP)") (class "Default")
      (node (ref "C27") (pin "1") (pinfunction "1_1") (pintype "passive"))
      (node (ref "IC2") (pin "16") (pinfunction "VPP_16") (pintype "bidirectional"))
    )
    (net (code "50") (name "Net-(J2-Pad3)") (class "Default")
      (node (ref "J2") (pin "3") (pinfunction "3_3") (pintype "passive"))
      (node (ref "R21") (pin "1") (pinfunction "1_1") (pintype "passive"))
    )
    (net (code "51") (name "Net-(PS1-EN)") (class "Default")
      (node (ref "C6") (pin "1") (pinfunction "1_1") (pintype "passive"))
      (node (ref "D1") (pin "C") (pinfunction "C_C") (pintype "passive"))
      (node (ref "D2") (pin "C") (pinfunction "C_C") (pintype "passive"))
      (node (ref "PS1") (pin "3") (pinfunction "VIN_3") (pintype "input"))
      (node (ref "PS1") (pin "4") (pinfunction "EN_4") (pintype "input"))
    )
    (net (code "52") (name "Net-(Q2-S1)") (class "Default")
      (node (ref "Q2") (pin "1") (pinfunction "S2_1") (pintype "passive"))
      (node (ref "Q2") (pin "3") (pinfunction "S1_3") (pintype "passive"))
      (node (ref "R7") (pin "2") (pinfunction "2_2") (pintype "passive"))
      (node (ref "R9") (pin "1") (pinfunction "1_1") (pintype "passive"))
    )
    (net (code "53") (name "Net-(Q4-S1)") (class "Default")
      (node (ref "Q4") (pin "1") (pinfunction "S2_1") (pintype "passive"))
      (node (ref "Q4") (pin "3") (pinfunction "S1_3") (pintype "passive"))
      (node (ref "R10") (pin "2") (pinfunction "2_2") (pintype "passive"))
      (node (ref "R12") (pin "1") (pinfunction "1_1") (pintype "passive"))
    )
    (net (code "54") (name "Net-(Q5-B)") (class "Default")
      (node (ref "Q5") (pin "1") (pinfunction "B_1") (pintype "passive"))
      (node (ref "R2") (pin "2") (pinfunction "2_2") (pintype "passive"))
    )
    (net (code "55") (name "Net-(Q6-B)") (class "Default")
      (node (ref "Q6") (pin "1") (pinfunction "B_1") (pintype "passive"))
      (node (ref "R1") (pin "2") (pinfunction "2_2") (pintype "passive"))
    )
    (net (code "56") (name "Net-(R6-Pad2)") (class "Default")
      (node (ref "R6") (pin "2") (pinfunction "2_2") (pintype "passive"))
      (node (ref "SJ9") (pin "2") (pinfunction "2_2") (pintype "passive"))
    )
    (net (code "57") (name "Net-(U1-CANH)") (class "Default")
      (node (ref "FL1") (pin "2") (pinfunction "2_2") (pintype "passive"))
      (node (ref "U1") (pin "7") (pinfunction "CANH_7") (pintype "input"))
    )
    (net (code "58") (name "Net-(U1-CANL)") (class "Default")
      (node (ref "FL1") (pin "3") (pinfunction "3_3") (pintype "passive"))
      (node (ref "U1") (pin "6") (pinfunction "CANL_6") (pintype "input"))
    )
    (net (code "59") (name "Net-(U2-C1+)") (class "Default")
      (node (ref "C25") (pin "1") (pinfunction "1_1") (pintype "passive"))
      (node (ref "U2") (pin "3") (pinfunction "C1+_3") (pintype "power_in"))
    )
    (net (code "60") (name "Net-(U2-C1-)") (class "Default")
      (node (ref "C25") (pin "2") (pinfunction "2_2") (pintype "passive"))
      (node (ref "U2") (pin "2") (pinfunction "C1-_2") (pintype "power_in"))
    )
    (net (code "61") (name "REFL") (class "Default")
      (node (ref "IC1") (pin "17") (pinfunction "REFL_STEP_17") (pintype "input"))
    )
    (net (code "62") (name "REFR") (class "Default")
      (node (ref "IC1") (pin "18") (pinfunction "REFR_DIR_18") (pintype "input"))
    )
    (net (code "63") (name "RESET") (class "Default")
      (node (ref "C2") (pin "1") (pinfunction "1_1") (pintype "passive"))
      (node (ref "Q5") (pin "3") (pinfunction "C_3") (pintype "passive"))
      (node (ref "R4") (pin "1") (pinfunction "1_1") (pintype "passive"))
      (node (ref "SW1") (pin "1") (pinfunction "1_1") (pintype "passive"))
      (node (ref "SW1") (pin "2") (pinfunction "2_2") (pintype "passive"))
      (node (ref "X2") (pin "3") (pinfunction "EN_3") (pintype "input"))
    )
    (net (code "64") (name "RTS") (class "Default")
      (node (ref "IC2") (pin "19") (pinfunction "RTS_19") (pintype "output"))
      (node (ref "Q5") (pin "2") (pinfunction "E_2") (pintype "passive"))
      (node (ref "R1") (pin "1") (pinfunction "1_1") (pintype "passive"))
    )
    (net (code "65") (name "RXD0") (class "Default")
      (node (ref "IC2") (pin "21") (pinfunction "TXD_21") (pintype "output"))
      (node (ref "X2") (pin "34") (pinfunction "RXD0_34") (pintype "input"))
    )
    (net (code "66") (name "SCK") (class "Default")
      (node (ref "IC1") (pin "14") (pinfunction "SCK_CFG2_14") (pintype "input"))
      (node (ref "R21") (pin "2") (pinfunction "2_2") (pintype "passive"))
      (node (ref "U3") (pin "2") (pinfunction "CLK_2") (pintype "input"))
      (node (ref "X2") (pin "13") (pinfunction "IO14/A2_6_13") (pintype "bidirectional"))
    )
    (net (code "67") (name "SCL") (class "Default")
      (node (ref "J2") (pin "7") (pinfunction "7_7") (pintype "passive"))
      (node (ref "R17") (pin "1") (pinfunction "1_1") (pintype "passive"))
      (node (ref "X2") (pin "36") (pinfunction "IO22_36") (pintype "bidirectional"))
    )
    (net (code "68") (name "SDA") (class "Default")
      (node (ref "J2") (pin "6") (pinfunction "6_6") (pintype "passive"))
      (node (ref "R13") (pin "1") (pinfunction "1_1") (pintype "passive"))
      (node (ref "X2") (pin "33") (pinfunction "IO21_33") (pintype "bidirectional"))
    )
    (net (code "69") (name "SRAH") (class "Default")
      (node (ref "IC1") (pin "8") (pinfunction "SRAH_8") (pintype "input"))
      (node (ref "R12") (pin "2") (pinfunction "2_2") (pintype "passive"))
    )
    (net (code "70") (name "SRAL") (class "Default")
      (node (ref "IC1") (pin "7") (pinfunction "SRAL_7") (pintype "input"))
      (node (ref "R11") (pin "2") (pinfunction "2_2") (pintype "passive"))
    )
    (net (code "71") (name "SRBH") (class "Default")
      (node (ref "IC1") (pin "9") (pinfunction "SRBH_9") (pintype "input"))
      (node (ref "R9") (pin "2") (pinfunction "2_2") (pintype "passive"))
    )
    (net (code "72") (name "SRBL") (class "Default")
      (node (ref "IC1") (pin "10") (pinfunction "SRBL_10") (pintype "input"))
      (node (ref "R8") (pin "2") (pinfunction "2_2") (pintype "passive"))
    )
    (net (code "73") (name "TMC_DIAG0") (class "Default")
      (node (ref "IC1") (pin "26") (pinfunction "DIAG0_SWN_26") (pintype "bidirectional"))
      (node (ref "X2") (pin "5") (pinfunction "IO39/SEN_VN/A1_3_5") (pintype "passive"))
    )
    (net (code "74") (name "TMC_DIAG1") (class "Default")
      (node (ref "IC1") (pin "27") (pinfunction "DIAG1_SWP_27") (pintype "bidirectional"))
      (node (ref "X2") (pin "4") (pinfunction "IO36/SEN_VP/A1_0_4") (pintype "passive"))
    )
    (net (code "75") (name "TXD0") (class "Default")
      (node (ref "IC2") (pin "20") (pinfunction "RXD_20") (pintype "input"))
      (node (ref "X2") (pin "35") (pinfunction "TXD0_35") (pintype "output"))
    )
    (net (code "76") (name "USBD+") (class "Default")
      (node (ref "D7") (pin "3") (pinfunction "3_3") (pintype "passive"))
      (node (ref "IC2") (pin "3") (pinfunction "D+_3") (pintype "bidirectional"))
      (node (ref "J4") (pin "3") (pinfunction "D+_3") (pintype "passive"))
    )
    (net (code "77") (name "USBD-") (class "Default")
      (node (ref "D7") (pin "4") (pinfunction "4_4") (pintype "passive"))
      (node (ref "IC2") (pin "4") (pinfunction "D-_4") (pintype "bidirectional"))
      (node (ref "J4") (pin "2") (pinfunction "D-_2") (pintype "passive"))
    )
    (net (code "78") (name "VBUS") (class "Default")
      (node (ref "D1") (pin "A") (pinfunction "A_A") (pintype "passive"))
      (node (ref "D7") (pin "2") (pinfunction "2_2") (pintype "passive"))
      (node (ref "IC2") (pin "8") (pinfunction "VBUS_8") (pintype "power_in"))
      (node (ref "J4") (pin "1") (pinfunction "VUSB_1") (pintype "passive"))
    )
    (net (code "79") (name "unconnected-(IC1-ENCA_CFG5-Pad24)") (class "Default")
      (node (ref "IC1") (pin "24") (pinfunction "ENCA_CFG5_24") (pintype "input"))
    )
    (net (code "80") (name "unconnected-(IC1-ENCB_CFG4-Pad23)") (class "Default")
      (node (ref "IC1") (pin "23") (pinfunction "ENCB_CFG4_23") (pintype "input"))
    )
    (net (code "81") (name "unconnected-(IC1-ENCN_CFG6-Pad25)") (class "Default")
      (node (ref "IC1") (pin "25") (pinfunction "ENCN_CFG6_25") (pintype "input"))
    )
    (net (code "82") (name "unconnected-(IC2A-#RST-Pad9)") (class "Default")
      (node (ref "IC2") (pin "9") (pinfunction "#RST_9") (pintype "bidirectional"))
    )
    (net (code "83") (name "unconnected-(IC2A-#SUSPEND-Pad15)") (class "Default")
      (node (ref "IC2") (pin "15") (pinfunction "#SUSPEND_15") (pintype "output"))
    )
    (net (code "84") (name "unconnected-(IC2A-CTS-Pad18)") (class "Default")
      (node (ref "IC2") (pin "18") (pinfunction "CTS_18") (pintype "input"))
    )
    (net (code "85") (name "unconnected-(IC2A-DCD-Pad24)") (class "Default")
      (node (ref "IC2") (pin "24") (pinfunction "DCD_24") (pintype "input"))
    )
    (net (code "86") (name "unconnected-(IC2A-DSR-Pad22)") (class "Default")
      (node (ref "IC2") (pin "22") (pinfunction "DSR_22") (pintype "input"))
    )
    (net (code "87") (name "unconnected-(IC2A-GPIO0{slash}TXLED-Pad14)") (class "Default")
      (node (ref "IC2") (pin "14") (pinfunction "GPIO0/TXLED_14") (pintype "bidirectional"))
    )
    (net (code "88") (name "unconnected-(IC2A-GPIO1{slash}RXLED-Pad13)") (class "Default")
      (node (ref "IC2") (pin "13") (pinfunction "GPIO1/RXLED_13") (pintype "bidirectional"))
    )
    (net (code "89") (name "unconnected-(IC2A-GPIO2-Pad12)") (class "Default")
      (node (ref "IC2") (pin "12") (pinfunction "GPIO2_12") (pintype "bidirectional"))
    )
    (net (code "90") (name "unconnected-(IC2A-GPIO3-Pad11)") (class "Default")
      (node (ref "IC2") (pin "11") (pinfunction "GPIO3_11") (pintype "bidirectional"))
    )
    (net (code "91") (name "unconnected-(IC2A-NC-Pad10)") (class "Default")
      (node (ref "IC2") (pin "10") (pinfunction "NC_10") (pintype "no_connect"))
    )
    (net (code "92") (name "unconnected-(IC2A-RI-Pad1)") (class "Default")
      (node (ref "IC2") (pin "1") (pinfunction "RI_1") (pintype "input"))
    )
    (net (code "93") (name "unconnected-(IC2A-SUSPEND-Pad17)") (class "Default")
      (node (ref "IC2") (pin "17") (pinfunction "SUSPEND_17") (pintype "output"))
    )
    (net (code "94") (name "unconnected-(J4-ID-Pad4)") (class "Default")
      (node (ref "J4") (pin "4") (pinfunction "ID_4") (pintype "passive"))
    )
    (net (code "95") (name "unconnected-(PS1-DNC8-Pad8)") (class "Default")
      (node (ref "PS1") (pin "8") (pinfunction "DNC8_8") (pintype "output"))
    )
    (net (code "96") (name "unconnected-(PS1-DNC9-Pad9)") (class "Default")
      (node (ref "PS1") (pin "9") (pinfunction "DNC9_9") (pintype "output"))
    )
    (net (code "97") (name "unconnected-(PS1-DNC10-Pad10)") (class "Default")
      (node (ref "PS1") (pin "10") (pinfunction "DNC10_10") (pintype "output"))
    )
    (net (code "98") (name "unconnected-(PS1-PGOOD-Pad5)") (class "Default")
      (node (ref "PS1") (pin "5") (pinfunction "PGOOD_5") (pintype "output"))
    )
    (net (code "99") (name "unconnected-(U1-STBY-Pad8)") (class "Default")
      (node (ref "U1") (pin "8") (pinfunction "STBY_8") (pintype "input"))
    )
    (net (code "100") (name "unconnected-(U3-PWM-Pad14)") (class "Default")
      (node (ref "U3") (pin "14") (pinfunction "PWM_14") (pintype "output"))
    )
    (net (code "101") (name "unconnected-(U3-TEST1-Pad5)") (class "Default")
      (node (ref "U3") (pin "5") (pinfunction "TEST1_5") (pintype "bidirectional"))
    )
    (net (code "102") (name "unconnected-(U3-TEST2-Pad6)") (class "Default")
      (node (ref "U3") (pin "6") (pinfunction "TEST2_6") (pintype "bidirectional"))
    )
    (net (code "103") (name "unconnected-(U3-TEST3-Pad7)") (class "Default")
      (node (ref "U3") (pin "7") (pinfunction "TEST3_7") (pintype "bidirectional"))
    )
    (net (code "104") (name "unconnected-(U3-TEST4-Pad8)") (class "Default")
      (node (ref "U3") (pin "8") (pinfunction "TEST4_8") (pintype "bidirectional"))
    )
    (net (code "105") (name "unconnected-(U3-TEST5-Pad9)") (class "Default")
      (node (ref "U3") (pin "9") (pinfunction "TEST5_9") (pintype "bidirectional"))
    )
    (net (code "106") (name "unconnected-(U3-TEST6-Pad10)") (class "Default")
      (node (ref "U3") (pin "10") (pinfunction "TEST6_10") (pintype "bidirectional"))
    )
    (net (code "107") (name "unconnected-(X2-CLK-Pad20)") (class "Default")
      (node (ref "X2") (pin "20") (pinfunction "CLK_20") (pintype "bidirectional"))
    )
    (net (code "108") (name "unconnected-(X2-CMD-Pad19)") (class "Default")
      (node (ref "X2") (pin "19") (pinfunction "CMD_19") (pintype "bidirectional"))
    )
    (net (code "109") (name "unconnected-(X2-I34{slash}A1_6-Pad6)") (class "Default")
      (node (ref "X2") (pin "6") (pinfunction "I34/A1_6_6") (pintype "bidirectional"))
    )
    (net (code "110") (name "unconnected-(X2-I35{slash}A1_7-Pad7)") (class "Default")
      (node (ref "X2") (pin "7") (pinfunction "I35/A1_7_7") (pintype "bidirectional"))
    )
    (net (code "111") (name "unconnected-(X2-IO23-Pad37)") (class "Default")
      (node (ref "X2") (pin "37") (pinfunction "IO23_37") (pintype "bidirectional"))
    )
    (net (code "112") (name "unconnected-(X2-SD0-Pad21)") (class "Default")
      (node (ref "X2") (pin "21") (pinfunction "SD0_21") (pintype "bidirectional"))
    )
    (net (code "113") (name "unconnected-(X2-SD1-Pad22)") (class "Default")
      (node (ref "X2") (pin "22") (pinfunction "SD1_22") (pintype "bidirectional"))
    )
    (net (code "114") (name "unconnected-(X2-SD2-Pad17)") (class "Default")
      (node (ref "X2") (pin "17") (pinfunction "SD2_17") (pintype "bidirectional"))
    )
    (net (code "115") (name "unconnected-(X2-SD3-Pad18)") (class "Default")
      (node (ref "X2") (pin "18") (pinfunction "SD3_18") (pintype "bidirectional"))
    )
  )
)
